# BladeCore-M54.net
KiCad netlist of a schematic drawn in EAGLE
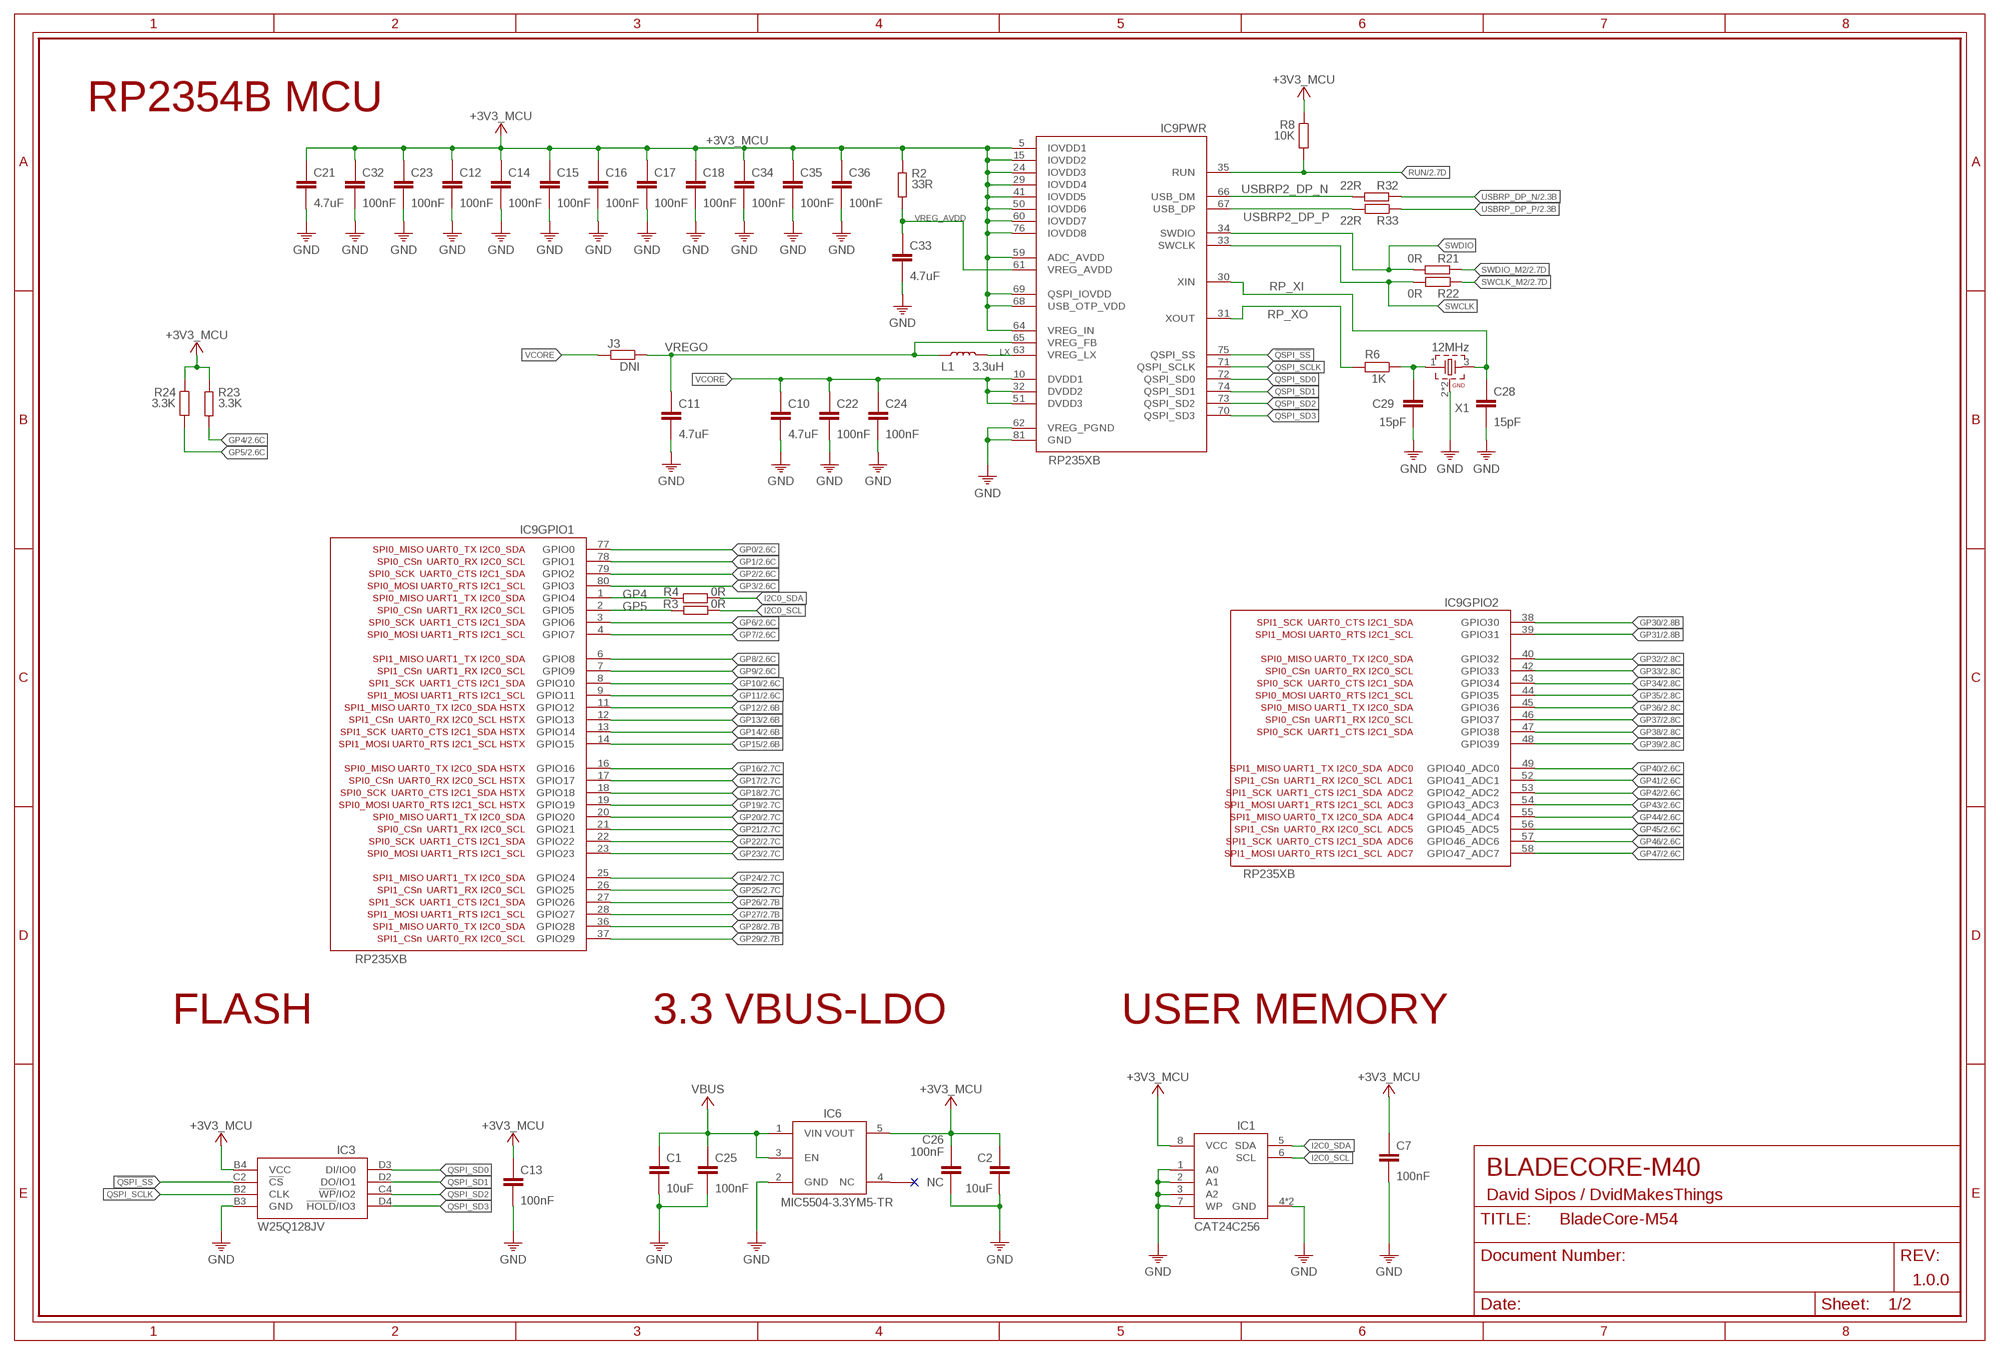
[diagram p0: schematic, sheet 1]
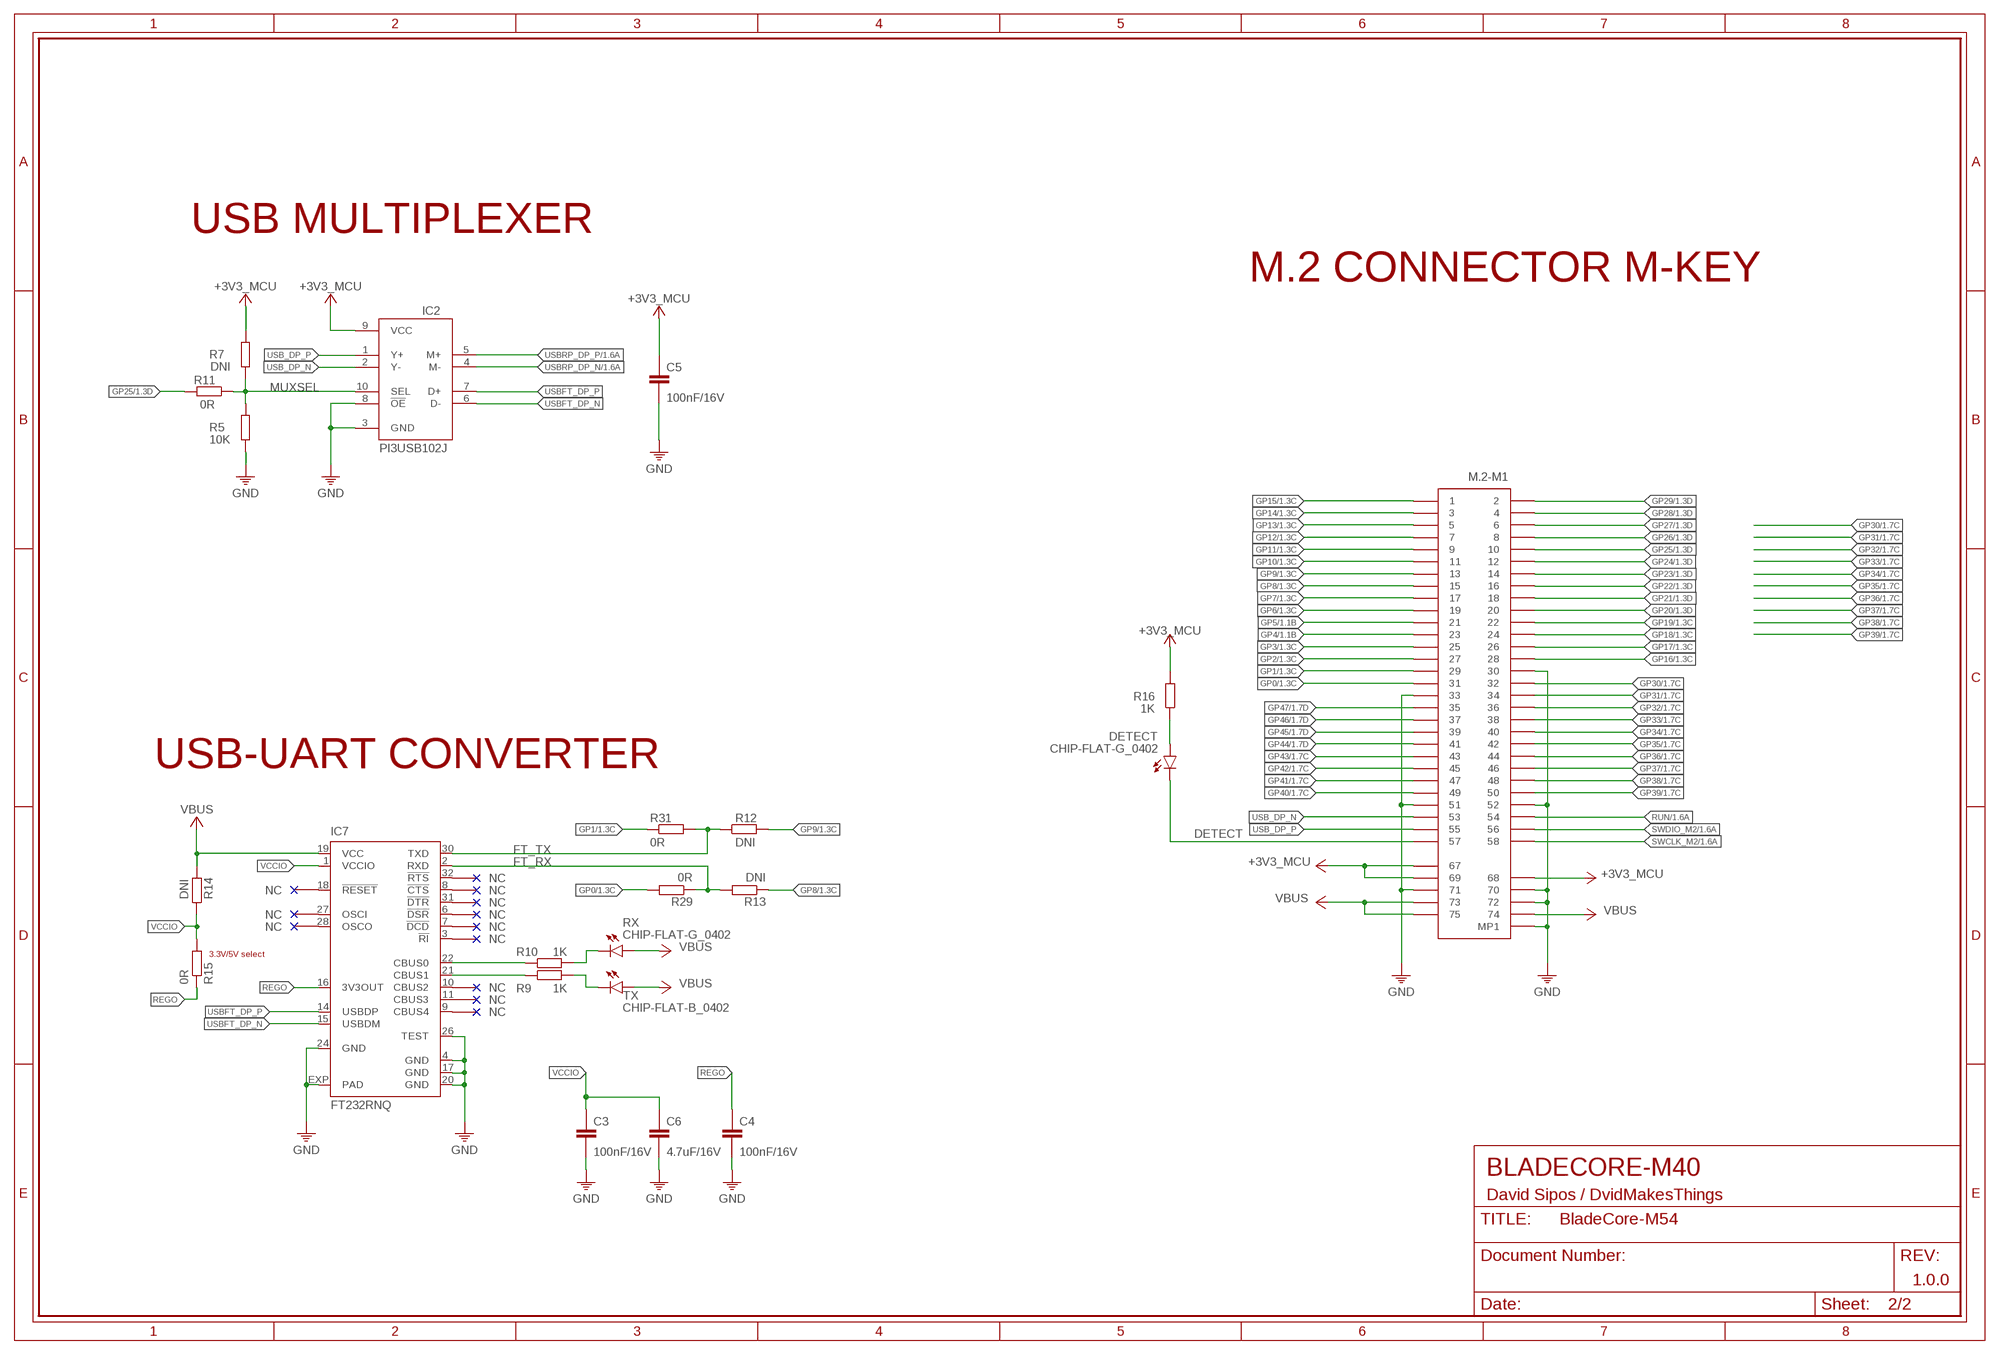
[diagram p1: schematic, sheet 2]

(export (version "E")
  (design (tool "Eeschema 10.0.6"))
  (components
    (comp (ref "C1")
      (value "10uF")
      (footprint "eagle-import:0805")
      (libsource (lib "eagle-import") (part "C0805"))
    )
    (comp (ref "C2")
      (value "10uF")
      (footprint "eagle-import:0805")
      (libsource (lib "eagle-import") (part "C0805"))
    )
    (comp (ref "C7")
      (value "100nF")
      (footprint "eagle-import:0201")
      (libsource (lib "eagle-import") (part "C-0201"))
    )
    (comp (ref "C10")
      (value "4.7uF")
      (footprint "eagle-import:0201")
      (libsource (lib "eagle-import") (part "C-0201"))
    )
    (comp (ref "C11")
      (value "4.7uF")
      (footprint "eagle-import:0201")
      (libsource (lib "eagle-import") (part "C-0201"))
    )
    (comp (ref "C12")
      (value "100nF")
      (footprint "eagle-import:0201")
      (libsource (lib "eagle-import") (part "C-0201"))
    )
    (comp (ref "C13")
      (value "100nF")
      (footprint "eagle-import:0201")
      (libsource (lib "eagle-import") (part "C-0201"))
    )
    (comp (ref "C14")
      (value "100nF")
      (footprint "eagle-import:0201")
      (libsource (lib "eagle-import") (part "C-0201"))
    )
    (comp (ref "C15")
      (value "100nF")
      (footprint "eagle-import:0201")
      (libsource (lib "eagle-import") (part "C-0201"))
    )
    (comp (ref "C16")
      (value "100nF")
      (footprint "eagle-import:0201")
      (libsource (lib "eagle-import") (part "C-0201"))
    )
    (comp (ref "C17")
      (value "100nF")
      (footprint "eagle-import:0201")
      (libsource (lib "eagle-import") (part "C-0201"))
    )
    (comp (ref "C18")
      (value "100nF")
      (footprint "eagle-import:0201")
      (libsource (lib "eagle-import") (part "C-0201"))
    )
    (comp (ref "C21")
      (value "4.7uF")
      (footprint "eagle-import:C0402")
      (libsource (lib "eagle-import") (part "C-0402"))
    )
    (comp (ref "C22")
      (value "100nF")
      (footprint "eagle-import:0201")
      (libsource (lib "eagle-import") (part "C-0201"))
    )
    (comp (ref "C23")
      (value "100nF")
      (footprint "eagle-import:0201")
      (libsource (lib "eagle-import") (part "C-0201"))
    )
    (comp (ref "C24")
      (value "100nF")
      (footprint "eagle-import:0201")
      (libsource (lib "eagle-import") (part "C-0201"))
    )
    (comp (ref "C25")
      (value "100nF")
      (footprint "eagle-import:0201")
      (libsource (lib "eagle-import") (part "C-0201"))
    )
    (comp (ref "C26")
      (value "100nF")
      (footprint "eagle-import:0201")
      (libsource (lib "eagle-import") (part "C-0201"))
    )
    (comp (ref "C28")
      (value "15pF")
      (footprint "eagle-import:0201")
      (libsource (lib "eagle-import") (part "C-0201"))
    )
    (comp (ref "C29")
      (value "15pF")
      (footprint "eagle-import:0201")
      (libsource (lib "eagle-import") (part "C-0201"))
    )
    (comp (ref "C32")
      (value "100nF")
      (footprint "eagle-import:0201")
      (libsource (lib "eagle-import") (part "C-0201"))
    )
    (comp (ref "C33")
      (value "4.7uF")
      (footprint "eagle-import:0201")
      (libsource (lib "eagle-import") (part "C-0201"))
    )
    (comp (ref "C34")
      (value "100nF")
      (footprint "eagle-import:0201")
      (libsource (lib "eagle-import") (part "C-0201"))
    )
    (comp (ref "C35")
      (value "100nF")
      (footprint "eagle-import:0201")
      (libsource (lib "eagle-import") (part "C-0201"))
    )
    (comp (ref "C36")
      (value "100nF")
      (footprint "eagle-import:0201")
      (libsource (lib "eagle-import") (part "C-0201"))
    )
    (comp (ref "IC1")
      (value "CAT24C512HU5IGT3")
      (footprint "eagle-import:SON50P300X200X50-9T130X140N")
      (libsource (lib "eagle-import") (part "CAT24C256-HU4"))
    )
    (comp (ref "IC3")
      (value "W25Q128JVCIQ TR")
      (footprint "eagle-import:BGA24C100P4X6_800X600X120N")
      (libsource (lib "eagle-import") (part "W25Q128JVC"))
    )
    (comp (ref "IC6")
      (value "MIC5504-3.3YM5-TR")
      (footprint "eagle-import:SOT23-5")
      (libsource (lib "eagle-import") (part "MIC5504-3.3YM5-TR"))
    )
    (comp (ref "IC9")
      (value "RP235XB")
      (footprint "eagle-import:QFN80-10X10")
      (libsource (lib "eagle-import") (part "RP235XB"))
    )
    (comp (ref "J3")
      (value "DNI")
      (footprint "eagle-import:R0201")
      (libsource (lib "eagle-import") (part "R0201"))
    )
    (comp (ref "L1")
      (value "3.3uH")
      (footprint "eagle-import:SRR5228A")
      (libsource (lib "eagle-import") (part "L"))
    )
    (comp (ref "R2")
      (value "33R")
      (footprint "eagle-import:R0201")
      (libsource (lib "eagle-import") (part "R0201"))
    )
    (comp (ref "R3")
      (value "0R")
      (footprint "eagle-import:R0201")
      (libsource (lib "eagle-import") (part "R0201"))
    )
    (comp (ref "R4")
      (value "0R")
      (footprint "eagle-import:R0201")
      (libsource (lib "eagle-import") (part "R0201"))
    )
    (comp (ref "R6")
      (value "1K")
      (footprint "eagle-import:R0201")
      (libsource (lib "eagle-import") (part "R0201"))
    )
    (comp (ref "R8")
      (value "10K")
      (footprint "eagle-import:R0201")
      (libsource (lib "eagle-import") (part "R0201"))
    )
    (comp (ref "R21")
      (value "0R")
      (footprint "eagle-import:R0201")
      (libsource (lib "eagle-import") (part "R0201"))
    )
    (comp (ref "R22")
      (value "0R")
      (footprint "eagle-import:R0201")
      (libsource (lib "eagle-import") (part "R0201"))
    )
    (comp (ref "R23")
      (value "3.3K")
      (footprint "eagle-import:R0201")
      (libsource (lib "eagle-import") (part "R0201"))
    )
    (comp (ref "R24")
      (value "3.3K")
      (footprint "eagle-import:R0201")
      (libsource (lib "eagle-import") (part "R0201"))
    )
    (comp (ref "R32")
      (value "22R")
      (footprint "eagle-import:R0201")
      (libsource (lib "eagle-import") (part "R0201"))
    )
    (comp (ref "R33")
      (value "22R")
      (footprint "eagle-import:R0201")
      (libsource (lib "eagle-import") (part "R0201"))
    )
    (comp (ref "X1")
      (value "12MHz")
      (footprint "eagle-import:WE-XTAL_CFPX-180")
      (fields (field (name "TOLERANCE") "±20ppm"))
      (libsource (lib "eagle-import") (part "WE-XTAL_CFPX-180_830069944"))
    )
    (comp (ref "C3")
      (value "100nF/16V")
      (footprint "eagle-import:0201")
      (libsource (lib "eagle-import") (part "C-0201"))
    )
    (comp (ref "C4")
      (value "100nF/16V")
      (footprint "eagle-import:0201")
      (libsource (lib "eagle-import") (part "C-0201"))
    )
    (comp (ref "C5")
      (value "100nF/16V")
      (footprint "eagle-import:0201")
      (libsource (lib "eagle-import") (part "C-0201"))
    )
    (comp (ref "C6")
      (value "4.7uF/16V")
      (footprint "eagle-import:0201")
      (libsource (lib "eagle-import") (part "C-0201"))
    )
    (comp (ref "DETECT")
      (value "CHIP-FLAT-G_0402")
      (footprint "eagle-import:LEDC1005X25N_FLAT-G")
      (libsource (lib "eagle-import") (part "CHIP-FLAT-G_0402"))
    )
    (comp (ref "IC2")
      (value "PI3USB102J")
      (footprint "eagle-import:QFN40P120X140X35-10N")
      (libsource (lib "eagle-import") (part "PI3USB102JXUCEX"))
    )
    (comp (ref "IC7")
      (value "FT232RNQ")
      (footprint "eagle-import:QFN32")
      (libsource (lib "eagle-import") (part "FT232RQ"))
    )
    (comp (ref "M.2-M1")
      (value "M.2-M-KEY")
      (footprint "eagle-import:M.2-M-KEY")
      (libsource (lib "eagle-import") (part "M.2-M-KEY"))
    )
    (comp (ref "R5")
      (value "10K")
      (footprint "eagle-import:R0201")
      (libsource (lib "eagle-import") (part "R0201"))
    )
    (comp (ref "R7")
      (value "DNI")
      (footprint "eagle-import:R0201")
      (libsource (lib "eagle-import") (part "R0201"))
    )
    (comp (ref "R9")
      (value "1K")
      (footprint "eagle-import:R0201")
      (libsource (lib "eagle-import") (part "R0201"))
    )
    (comp (ref "R10")
      (value "1K")
      (footprint "eagle-import:R0201")
      (libsource (lib "eagle-import") (part "R0201"))
    )
    (comp (ref "R11")
      (value "0R")
      (footprint "eagle-import:R0201")
      (libsource (lib "eagle-import") (part "R0201"))
    )
    (comp (ref "R12")
      (value "DNI")
      (footprint "eagle-import:R0201")
      (libsource (lib "eagle-import") (part "R0201"))
    )
    (comp (ref "R13")
      (value "DNI")
      (footprint "eagle-import:R0201")
      (libsource (lib "eagle-import") (part "R0201"))
    )
    (comp (ref "R14")
      (value "DNI")
      (footprint "eagle-import:R0201")
      (libsource (lib "eagle-import") (part "R0201"))
    )
    (comp (ref "R15")
      (value "0R")
      (footprint "eagle-import:R0201")
      (libsource (lib "eagle-import") (part "R0201"))
    )
    (comp (ref "R16")
      (value "1K")
      (footprint "eagle-import:R0201")
      (libsource (lib "eagle-import") (part "R0201"))
    )
    (comp (ref "R29")
      (value "0R")
      (footprint "eagle-import:R0201")
      (libsource (lib "eagle-import") (part "R0201"))
    )
    (comp (ref "R31")
      (value "0R")
      (footprint "eagle-import:R0201")
      (libsource (lib "eagle-import") (part "R0201"))
    )
    (comp (ref "RX")
      (value "CHIP-FLAT-G_0402")
      (footprint "eagle-import:LEDC1005X25N_FLAT-G")
      (libsource (lib "eagle-import") (part "CHIP-FLAT-G_0402"))
    )
    (comp (ref "TX")
      (value "CHIP-FLAT-B_0402")
      (footprint "eagle-import:LEDC1005X25N_FLAT-B")
      (libsource (lib "eagle-import") (part "CHIP-FLAT-B_0402"))
    )
  )
  (nets
    (net (code "1") (name "+3V3_MCU") (class "Default")
      (node (ref "C12") (pin "1") (pinfunction "1_1") (pintype "passive"))
      (node (ref "C13") (pin "1") (pinfunction "1_1") (pintype "passive"))
      (node (ref "C14") (pin "1") (pinfunction "1_1") (pintype "passive"))
      (node (ref "C15") (pin "1") (pinfunction "1_1") (pintype "passive"))
      (node (ref "C16") (pin "1") (pinfunction "1_1") (pintype "passive"))
      (node (ref "C17") (pin "1") (pinfunction "1_1") (pintype "passive"))
      (node (ref "C18") (pin "1") (pinfunction "1_1") (pintype "passive"))
      (node (ref "C2") (pin "1") (pinfunction "1_1") (pintype "passive"))
      (node (ref "C21") (pin "1") (pinfunction "1_1") (pintype "passive"))
      (node (ref "C23") (pin "1") (pinfunction "1_1") (pintype "passive"))
      (node (ref "C26") (pin "1") (pinfunction "1_1") (pintype "passive"))
      (node (ref "C32") (pin "1") (pinfunction "1_1") (pintype "passive"))
      (node (ref "C34") (pin "1") (pinfunction "1_1") (pintype "passive"))
      (node (ref "C35") (pin "1") (pinfunction "1_1") (pintype "passive"))
      (node (ref "C36") (pin "1") (pinfunction "1_1") (pintype "passive"))
      (node (ref "C5") (pin "1") (pinfunction "1_1") (pintype "passive"))
      (node (ref "C7") (pin "1") (pinfunction "1_1") (pintype "passive"))
      (node (ref "IC1") (pin "8") (pinfunction "VCC_8") (pintype "power_in"))
      (node (ref "IC2") (pin "9") (pinfunction "VCC_9") (pintype "power_in"))
      (node (ref "IC3") (pin "B4") (pinfunction "VCC_B4") (pintype "power_in"))
      (node (ref "IC6") (pin "5") (pinfunction "VOUT_5") (pintype "bidirectional"))
      (node (ref "IC9") (pin "15") (pinfunction "IOVDD2_15") (pintype "power_in"))
      (node (ref "IC9") (pin "24") (pinfunction "IOVDD3_24") (pintype "power_in"))
      (node (ref "IC9") (pin "29") (pinfunction "IOVDD4_29") (pintype "power_in"))
      (node (ref "IC9") (pin "41") (pinfunction "IOVDD5_41") (pintype "power_in"))
      (node (ref "IC9") (pin "5") (pinfunction "IOVDD1_5") (pintype "power_in"))
      (node (ref "IC9") (pin "50") (pinfunction "IOVDD6_50") (pintype "power_in"))
      (node (ref "IC9") (pin "59") (pinfunction "ADC_AVDD_59") (pintype "power_in"))
      (node (ref "IC9") (pin "60") (pinfunction "IOVDD7_60") (pintype "power_in"))
      (node (ref "IC9") (pin "64") (pinfunction "VREG_IN_64") (pintype "power_in"))
      (node (ref "IC9") (pin "68") (pinfunction "USB_OTP_VDD_68") (pintype "power_in"))
      (node (ref "IC9") (pin "69") (pinfunction "QSPI_IOVDD_69") (pintype "power_in"))
      (node (ref "IC9") (pin "76") (pinfunction "IOVDD8_76") (pintype "power_in"))
      (node (ref "M.2-M1") (pin "P$67") (pinfunction "67_P$67") (pintype "bidirectional"))
      (node (ref "M.2-M1") (pin "P$68") (pinfunction "68_P$68") (pintype "bidirectional"))
      (node (ref "M.2-M1") (pin "P$69") (pinfunction "69_P$69") (pintype "bidirectional"))
      (node (ref "R16") (pin "2") (pinfunction "2_2") (pintype "passive"))
      (node (ref "R2") (pin "1") (pinfunction "1_1") (pintype "passive"))
      (node (ref "R23") (pin "1") (pinfunction "1_1") (pintype "passive"))
      (node (ref "R24") (pin "1") (pinfunction "1_1") (pintype "passive"))
      (node (ref "R7") (pin "2") (pinfunction "2_2") (pintype "passive"))
      (node (ref "R8") (pin "1") (pinfunction "1_1") (pintype "passive"))
    )
    (net (code "2") (name "DETECT") (class "Default")
      (node (ref "DETECT") (pin "C") (pinfunction "C_C") (pintype "passive"))
      (node (ref "M.2-M1") (pin "P$57") (pinfunction "57_P$57") (pintype "bidirectional"))
    )
    (net (code "3") (name "FT_RX") (class "Default")
      (node (ref "IC7") (pin "2") (pinfunction "RXD_2") (pintype "input"))
      (node (ref "R13") (pin "2") (pinfunction "2_2") (pintype "passive"))
      (node (ref "R29") (pin "1") (pinfunction "1_1") (pintype "passive"))
    )
    (net (code "4") (name "FT_TX") (class "Default")
      (node (ref "IC7") (pin "30") (pinfunction "TXD_30") (pintype "output"))
      (node (ref "R12") (pin "1") (pinfunction "1_1") (pintype "passive"))
      (node (ref "R31") (pin "2") (pinfunction "2_2") (pintype "passive"))
    )
    (net (code "5") (name "GND") (class "Default")
      (node (ref "C1") (pin "2") (pinfunction "2_2") (pintype "passive"))
      (node (ref "C10") (pin "2") (pinfunction "2_2") (pintype "passive"))
      (node (ref "C11") (pin "2") (pinfunction "2_2") (pintype "passive"))
      (node (ref "C12") (pin "2") (pinfunction "2_2") (pintype "passive"))
      (node (ref "C13") (pin "2") (pinfunction "2_2") (pintype "passive"))
      (node (ref "C14") (pin "2") (pinfunction "2_2") (pintype "passive"))
      (node (ref "C15") (pin "2") (pinfunction "2_2") (pintype "passive"))
      (node (ref "C16") (pin "2") (pinfunction "2_2") (pintype "passive"))
      (node (ref "C17") (pin "2") (pinfunction "2_2") (pintype "passive"))
      (node (ref "C18") (pin "2") (pinfunction "2_2") (pintype "passive"))
      (node (ref "C2") (pin "2") (pinfunction "2_2") (pintype "passive"))
      (node (ref "C21") (pin "2") (pinfunction "2_2") (pintype "passive"))
      (node (ref "C22") (pin "2") (pinfunction "2_2") (pintype "passive"))
      (node (ref "C23") (pin "2") (pinfunction "2_2") (pintype "passive"))
      (node (ref "C24") (pin "2") (pinfunction "2_2") (pintype "passive"))
      (node (ref "C25") (pin "2") (pinfunction "2_2") (pintype "passive"))
      (node (ref "C26") (pin "2") (pinfunction "2_2") (pintype "passive"))
      (node (ref "C28") (pin "2") (pinfunction "2_2") (pintype "passive"))
      (node (ref "C29") (pin "2") (pinfunction "2_2") (pintype "passive"))
      (node (ref "C3") (pin "2") (pinfunction "2_2") (pintype "passive"))
      (node (ref "C32") (pin "2") (pinfunction "2_2") (pintype "passive"))
      (node (ref "C33") (pin "2") (pinfunction "2_2") (pintype "passive"))
      (node (ref "C34") (pin "2") (pinfunction "2_2") (pintype "passive"))
      (node (ref "C35") (pin "2") (pinfunction "2_2") (pintype "passive"))
      (node (ref "C36") (pin "2") (pinfunction "2_2") (pintype "passive"))
      (node (ref "C4") (pin "2") (pinfunction "2_2") (pintype "passive"))
      (node (ref "C5") (pin "2") (pinfunction "2_2") (pintype "passive"))
      (node (ref "C6") (pin "2") (pinfunction "2_2") (pintype "passive"))
      (node (ref "C7") (pin "2") (pinfunction "2_2") (pintype "passive"))
      (node (ref "IC1") (pin "1") (pinfunction "A0_1") (pintype "bidirectional"))
      (node (ref "IC1") (pin "2") (pinfunction "A1_2") (pintype "bidirectional"))
      (node (ref "IC1") (pin "3") (pinfunction "A2_3") (pintype "bidirectional"))
      (node (ref "IC1") (pin "4") (pinfunction "GND_4") (pintype "power_in"))
      (node (ref "IC1") (pin "7") (pinfunction "WP_7") (pintype "bidirectional"))
      (node (ref "IC1") (pin "9") (pinfunction "GND_9") (pintype "power_in"))
      (node (ref "IC2") (pin "3") (pinfunction "GND_3") (pintype "power_in"))
      (node (ref "IC2") (pin "8") (pinfunction "~{OE}_8") (pintype "input"))
      (node (ref "IC3") (pin "B3") (pinfunction "GND_B3") (pintype "power_in"))
      (node (ref "IC6") (pin "2") (pinfunction "GND_2") (pintype "bidirectional"))
      (node (ref "IC7") (pin "17") (pinfunction "GND_17") (pintype "power_in"))
      (node (ref "IC7") (pin "20") (pinfunction "GND_20") (pintype "power_in"))
      (node (ref "IC7") (pin "24") (pinfunction "GND_24") (pintype "power_in"))
      (node (ref "IC7") (pin "26") (pinfunction "TEST_26") (pintype "input"))
      (node (ref "IC7") (pin "4") (pinfunction "GND_4") (pintype "power_in"))
      (node (ref "IC7") (pin "EXP") (pinfunction "PAD_EXP") (pintype "power_in"))
      (node (ref "IC9") (pin "62") (pinfunction "VREG_PGND_62") (pintype "power_in"))
      (node (ref "IC9") (pin "81") (pinfunction "GND_81") (pintype "power_in"))
      (node (ref "M.2-M1") (pin "MT1") (pinfunction "MP1_MT1") (pintype "bidirectional"))
      (node (ref "M.2-M1") (pin "P$30") (pinfunction "30_P$30") (pintype "bidirectional"))
      (node (ref "M.2-M1") (pin "P$33") (pinfunction "33_P$33") (pintype "bidirectional"))
      (node (ref "M.2-M1") (pin "P$51") (pinfunction "51_P$51") (pintype "bidirectional"))
      (node (ref "M.2-M1") (pin "P$52") (pinfunction "52_P$52") (pintype "bidirectional"))
      (node (ref "M.2-M1") (pin "P$70") (pinfunction "70_P$70") (pintype "bidirectional"))
      (node (ref "M.2-M1") (pin "P$71") (pinfunction "71_P$71") (pintype "bidirectional"))
      (node (ref "M.2-M1") (pin "P$72") (pinfunction "72_P$72") (pintype "bidirectional"))
      (node (ref "R5") (pin "1") (pinfunction "1_1") (pintype "passive"))
      (node (ref "X1") (pin "2") (pinfunction "GND_2") (pintype "passive"))
      (node (ref "X1") (pin "4") (pinfunction "GND_4") (pintype "passive"))
    )
    (net (code "6") (name "GP0") (class "Default")
      (node (ref "IC9") (pin "77") (pinfunction "GPIO0_77") (pintype "bidirectional"))
      (node (ref "M.2-M1") (pin "P$31") (pinfunction "31_P$31") (pintype "bidirectional"))
      (node (ref "R29") (pin "2") (pinfunction "2_2") (pintype "passive"))
    )
    (net (code "7") (name "GP1") (class "Default")
      (node (ref "IC9") (pin "78") (pinfunction "GPIO1_78") (pintype "bidirectional"))
      (node (ref "M.2-M1") (pin "P$29") (pinfunction "29_P$29") (pintype "bidirectional"))
      (node (ref "R31") (pin "1") (pinfunction "1_1") (pintype "passive"))
    )
    (net (code "8") (name "GP2") (class "Default")
      (node (ref "IC9") (pin "79") (pinfunction "GPIO2_79") (pintype "bidirectional"))
      (node (ref "M.2-M1") (pin "P$27") (pinfunction "27_P$27") (pintype "bidirectional"))
    )
    (net (code "9") (name "GP3") (class "Default")
      (node (ref "IC9") (pin "80") (pinfunction "GPIO3_80") (pintype "bidirectional"))
      (node (ref "M.2-M1") (pin "P$25") (pinfunction "25_P$25") (pintype "bidirectional"))
    )
    (net (code "10") (name "GP4") (class "Default")
      (node (ref "IC9") (pin "1") (pinfunction "GPIO4_1") (pintype "bidirectional"))
      (node (ref "M.2-M1") (pin "P$23") (pinfunction "23_P$23") (pintype "bidirectional"))
      (node (ref "R23") (pin "2") (pinfunction "2_2") (pintype "passive"))
      (node (ref "R4") (pin "1") (pinfunction "1_1") (pintype "passive"))
    )
    (net (code "11") (name "GP5") (class "Default")
      (node (ref "IC9") (pin "2") (pinfunction "GPIO5_2") (pintype "bidirectional"))
      (node (ref "M.2-M1") (pin "P$21") (pinfunction "21_P$21") (pintype "bidirectional"))
      (node (ref "R24") (pin "2") (pinfunction "2_2") (pintype "passive"))
      (node (ref "R3") (pin "1") (pinfunction "1_1") (pintype "passive"))
    )
    (net (code "12") (name "GP6") (class "Default")
      (node (ref "IC9") (pin "3") (pinfunction "GPIO6_3") (pintype "bidirectional"))
      (node (ref "M.2-M1") (pin "P$19") (pinfunction "19_P$19") (pintype "bidirectional"))
    )
    (net (code "13") (name "GP7") (class "Default")
      (node (ref "IC9") (pin "4") (pinfunction "GPIO7_4") (pintype "bidirectional"))
      (node (ref "M.2-M1") (pin "P$17") (pinfunction "17_P$17") (pintype "bidirectional"))
    )
    (net (code "14") (name "GP8") (class "Default")
      (node (ref "IC9") (pin "6") (pinfunction "GPIO8_6") (pintype "bidirectional"))
      (node (ref "M.2-M1") (pin "P$15") (pinfunction "15_P$15") (pintype "bidirectional"))
      (node (ref "R13") (pin "1") (pinfunction "1_1") (pintype "passive"))
    )
    (net (code "15") (name "GP9") (class "Default")
      (node (ref "IC9") (pin "7") (pinfunction "GPIO9_7") (pintype "bidirectional"))
      (node (ref "M.2-M1") (pin "P$13") (pinfunction "13_P$13") (pintype "bidirectional"))
      (node (ref "R12") (pin "2") (pinfunction "2_2") (pintype "passive"))
    )
    (net (code "16") (name "GP10") (class "Default")
      (node (ref "IC9") (pin "8") (pinfunction "GPIO10_8") (pintype "bidirectional"))
      (node (ref "M.2-M1") (pin "P$11") (pinfunction "11_P$11") (pintype "bidirectional"))
    )
    (net (code "17") (name "GP11") (class "Default")
      (node (ref "IC9") (pin "9") (pinfunction "GPIO11_9") (pintype "bidirectional"))
      (node (ref "M.2-M1") (pin "P$9") (pinfunction "9_P$9") (pintype "bidirectional"))
    )
    (net (code "18") (name "GP12") (class "Default")
      (node (ref "IC9") (pin "11") (pinfunction "GPIO12_11") (pintype "bidirectional"))
      (node (ref "M.2-M1") (pin "P$7") (pinfunction "7_P$7") (pintype "bidirectional"))
    )
    (net (code "19") (name "GP13") (class "Default")
      (node (ref "IC9") (pin "12") (pinfunction "GPIO13_12") (pintype "bidirectional"))
      (node (ref "M.2-M1") (pin "P$5") (pinfunction "5_P$5") (pintype "bidirectional"))
    )
    (net (code "20") (name "GP14") (class "Default")
      (node (ref "IC9") (pin "13") (pinfunction "GPIO14_13") (pintype "bidirectional"))
      (node (ref "M.2-M1") (pin "P$3") (pinfunction "3_P$3") (pintype "bidirectional"))
    )
    (net (code "21") (name "GP15") (class "Default")
      (node (ref "IC9") (pin "14") (pinfunction "GPIO15_14") (pintype "bidirectional"))
      (node (ref "M.2-M1") (pin "P$1") (pinfunction "1_P$1") (pintype "bidirectional"))
    )
    (net (code "22") (name "GP16") (class "Default")
      (node (ref "IC9") (pin "16") (pinfunction "GPIO16_16") (pintype "bidirectional"))
      (node (ref "M.2-M1") (pin "P$28") (pinfunction "28_P$28") (pintype "bidirectional"))
    )
    (net (code "23") (name "GP17") (class "Default")
      (node (ref "IC9") (pin "17") (pinfunction "GPIO17_17") (pintype "bidirectional"))
      (node (ref "M.2-M1") (pin "P$26") (pinfunction "26_P$26") (pintype "bidirectional"))
    )
    (net (code "24") (name "GP18") (class "Default")
      (node (ref "IC9") (pin "18") (pinfunction "GPIO18_18") (pintype "bidirectional"))
      (node (ref "M.2-M1") (pin "P$24") (pinfunction "24_P$24") (pintype "bidirectional"))
    )
    (net (code "25") (name "GP19") (class "Default")
      (node (ref "IC9") (pin "19") (pinfunction "GPIO19_19") (pintype "bidirectional"))
      (node (ref "M.2-M1") (pin "P$22") (pinfunction "22_P$22") (pintype "bidirectional"))
    )
    (net (code "26") (name "GP20") (class "Default")
      (node (ref "IC9") (pin "20") (pinfunction "GPIO20_20") (pintype "bidirectional"))
      (node (ref "M.2-M1") (pin "P$20") (pinfunction "20_P$20") (pintype "bidirectional"))
    )
    (net (code "27") (name "GP21") (class "Default")
      (node (ref "IC9") (pin "21") (pinfunction "GPIO21_21") (pintype "bidirectional"))
      (node (ref "M.2-M1") (pin "P$18") (pinfunction "18_P$18") (pintype "bidirectional"))
    )
    (net (code "28") (name "GP22") (class "Default")
      (node (ref "IC9") (pin "22") (pinfunction "GPIO22_22") (pintype "bidirectional"))
      (node (ref "M.2-M1") (pin "P$16") (pinfunction "16_P$16") (pintype "bidirectional"))
    )
    (net (code "29") (name "GP23") (class "Default")
      (node (ref "IC9") (pin "23") (pinfunction "GPIO23_23") (pintype "bidirectional"))
      (node (ref "M.2-M1") (pin "P$14") (pinfunction "14_P$14") (pintype "bidirectional"))
    )
    (net (code "30") (name "GP24") (class "Default")
      (node (ref "IC9") (pin "25") (pinfunction "GPIO24_25") (pintype "bidirectional"))
      (node (ref "M.2-M1") (pin "P$12") (pinfunction "12_P$12") (pintype "bidirectional"))
    )
    (net (code "31") (name "GP25") (class "Default")
      (node (ref "IC9") (pin "26") (pinfunction "GPIO25_26") (pintype "bidirectional"))
      (node (ref "M.2-M1") (pin "P$10") (pinfunction "10_P$10") (pintype "bidirectional"))
      (node (ref "R11") (pin "2") (pinfunction "2_2") (pintype "passive"))
    )
    (net (code "32") (name "GP26") (class "Default")
      (node (ref "IC9") (pin "27") (pinfunction "GPIO26_27") (pintype "bidirectional"))
      (node (ref "M.2-M1") (pin "P$8") (pinfunction "8_P$8") (pintype "bidirectional"))
    )
    (net (code "33") (name "GP27") (class "Default")
      (node (ref "IC9") (pin "28") (pinfunction "GPIO27_28") (pintype "bidirectional"))
      (node (ref "M.2-M1") (pin "P$6") (pinfunction "6_P$6") (pintype "bidirectional"))
    )
    (net (code "34") (name "GP28") (class "Default")
      (node (ref "IC9") (pin "36") (pinfunction "GPIO28_36") (pintype "bidirectional"))
      (node (ref "M.2-M1") (pin "P$4") (pinfunction "4_P$4") (pintype "bidirectional"))
    )
    (net (code "35") (name "GP29") (class "Default")
      (node (ref "IC9") (pin "37") (pinfunction "GPIO29_37") (pintype "bidirectional"))
      (node (ref "M.2-M1") (pin "P$2") (pinfunction "2_P$2") (pintype "bidirectional"))
    )
    (net (code "36") (name "GP30") (class "Default")
      (node (ref "IC9") (pin "38") (pinfunction "GPIO30_38") (pintype "bidirectional"))
      (node (ref "M.2-M1") (pin "P$32") (pinfunction "32_P$32") (pintype "bidirectional"))
    )
    (net (code "37") (name "GP31") (class "Default")
      (node (ref "IC9") (pin "39") (pinfunction "GPIO31_39") (pintype "bidirectional"))
      (node (ref "M.2-M1") (pin "P$34") (pinfunction "34_P$34") (pintype "bidirectional"))
    )
    (net (code "38") (name "GP32") (class "Default")
      (node (ref "IC9") (pin "40") (pinfunction "GPIO32_40") (pintype "bidirectional"))
      (node (ref "M.2-M1") (pin "P$36") (pinfunction "36_P$36") (pintype "bidirectional"))
    )
    (net (code "39") (name "GP33") (class "Default")
      (node (ref "IC9") (pin "42") (pinfunction "GPIO33_42") (pintype "bidirectional"))
      (node (ref "M.2-M1") (pin "P$38") (pinfunction "38_P$38") (pintype "bidirectional"))
    )
    (net (code "40") (name "GP34") (class "Default")
      (node (ref "IC9") (pin "43") (pinfunction "GPIO34_43") (pintype "bidirectional"))
      (node (ref "M.2-M1") (pin "P$40") (pinfunction "40_P$40") (pintype "bidirectional"))
    )
    (net (code "41") (name "GP35") (class "Default")
      (node (ref "IC9") (pin "44") (pinfunction "GPIO35_44") (pintype "bidirectional"))
      (node (ref "M.2-M1") (pin "P$42") (pinfunction "42_P$42") (pintype "bidirectional"))
    )
    (net (code "42") (name "GP36") (class "Default")
      (node (ref "IC9") (pin "45") (pinfunction "GPIO36_45") (pintype "bidirectional"))
      (node (ref "M.2-M1") (pin "P$44") (pinfunction "44_P$44") (pintype "bidirectional"))
    )
    (net (code "43") (name "GP37") (class "Default")
      (node (ref "IC9") (pin "46") (pinfunction "GPIO37_46") (pintype "bidirectional"))
      (node (ref "M.2-M1") (pin "P$46") (pinfunction "46_P$46") (pintype "bidirectional"))
    )
    (net (code "44") (name "GP38") (class "Default")
      (node (ref "IC9") (pin "47") (pinfunction "GPIO38_47") (pintype "bidirectional"))
      (node (ref "M.2-M1") (pin "P$48") (pinfunction "48_P$48") (pintype "bidirectional"))
    )
    (net (code "45") (name "GP39") (class "Default")
      (node (ref "IC9") (pin "48") (pinfunction "GPIO39_48") (pintype "bidirectional"))
      (node (ref "M.2-M1") (pin "P$50") (pinfunction "50_P$50") (pintype "bidirectional"))
    )
    (net (code "46") (name "GP40") (class "Default")
      (node (ref "IC9") (pin "49") (pinfunction "GPIO40_ADC0_49") (pintype "bidirectional"))
      (node (ref "M.2-M1") (pin "P$49") (pinfunction "49_P$49") (pintype "bidirectional"))
    )
    (net (code "47") (name "GP41") (class "Default")
      (node (ref "IC9") (pin "52") (pinfunction "GPIO41_ADC1_52") (pintype "bidirectional"))
      (node (ref "M.2-M1") (pin "P$47") (pinfunction "47_P$47") (pintype "bidirectional"))
    )
    (net (code "48") (name "GP42") (class "Default")
      (node (ref "IC9") (pin "53") (pinfunction "GPIO42_ADC2_53") (pintype "bidirectional"))
      (node (ref "M.2-M1") (pin "P$45") (pinfunction "45_P$45") (pintype "bidirectional"))
    )
    (net (code "49") (name "GP43") (class "Default")
      (node (ref "IC9") (pin "54") (pinfunction "GPIO43_ADC3_54") (pintype "bidirectional"))
      (node (ref "M.2-M1") (pin "P$43") (pinfunction "43_P$43") (pintype "bidirectional"))
    )
    (net (code "50") (name "GP44") (class "Default")
      (node (ref "IC9") (pin "55") (pinfunction "GPIO44_ADC4_55") (pintype "bidirectional"))
      (node (ref "M.2-M1") (pin "P$41") (pinfunction "41_P$41") (pintype "bidirectional"))
    )
    (net (code "51") (name "GP45") (class "Default")
      (node (ref "IC9") (pin "56") (pinfunction "GPIO45_ADC5_56") (pintype "bidirectional"))
      (node (ref "M.2-M1") (pin "P$39") (pinfunction "39_P$39") (pintype "bidirectional"))
    )
    (net (code "52") (name "GP46") (class "Default")
      (node (ref "IC9") (pin "57") (pinfunction "GPIO46_ADC6_57") (pintype "bidirectional"))
      (node (ref "M.2-M1") (pin "P$37") (pinfunction "37_P$37") (pintype "bidirectional"))
    )
    (net (code "53") (name "GP47") (class "Default")
      (node (ref "IC9") (pin "58") (pinfunction "GPIO47_ADC7_58") (pintype "bidirectional"))
      (node (ref "M.2-M1") (pin "P$35") (pinfunction "35_P$35") (pintype "bidirectional"))
    )
    (net (code "54") (name "I2C0_SCL") (class "Default")
      (node (ref "IC1") (pin "6") (pinfunction "SCL_6") (pintype "bidirectional"))
      (node (ref "R3") (pin "2") (pinfunction "2_2") (pintype "passive"))
    )
    (net (code "55") (name "I2C0_SDA") (class "Default")
      (node (ref "IC1") (pin "5") (pinfunction "SDA_5") (pintype "bidirectional"))
      (node (ref "R4") (pin "2") (pinfunction "2_2") (pintype "passive"))
    )
    (net (code "56") (name "LX") (class "Default")
      (node (ref "IC9") (pin "63") (pinfunction "VREG_LX_63") (pintype "power_in"))
      (node (ref "L1") (pin "2") (pinfunction "2_2") (pintype "passive"))
    )
    (net (code "57") (name "MUXSEL") (class "Default")
      (node (ref "IC2") (pin "10") (pinfunction "SEL_10") (pintype "input"))
      (node (ref "R11") (pin "1") (pinfunction "1_1") (pintype "passive"))
      (node (ref "R5") (pin "2") (pinfunction "2_2") (pintype "passive"))
      (node (ref "R7") (pin "1") (pinfunction "1_1") (pintype "passive"))
    )
    (net (code "58") (name "Net-(C29-Pad1)") (class "Default")
      (node (ref "C29") (pin "1") (pinfunction "1_1") (pintype "passive"))
      (node (ref "R6") (pin "1") (pinfunction "1_1") (pintype "passive"))
      (node (ref "X1") (pin "1") (pinfunction "1_1") (pintype "passive"))
    )
    (net (code "59") (name "Net-(DETECT-PadA)") (class "Default")
      (node (ref "DETECT") (pin "A") (pinfunction "A_A") (pintype "passive"))
      (node (ref "R16") (pin "1") (pinfunction "1_1") (pintype "passive"))
    )
    (net (code "60") (name "Net-(IC7-CBUS0)") (class "Default")
      (node (ref "IC7") (pin "22") (pinfunction "CBUS0_22") (pintype "bidirectional"))
      (node (ref "R10") (pin "1") (pinfunction "1_1") (pintype "passive"))
    )
    (net (code "61") (name "Net-(IC7-CBUS1)") (class "Default")
      (node (ref "IC7") (pin "21") (pinfunction "CBUS1_21") (pintype "bidirectional"))
      (node (ref "R9") (pin "1") (pinfunction "1_1") (pintype "passive"))
    )
    (net (code "62") (name "Net-(R9-Pad2)") (class "Default")
      (node (ref "R9") (pin "2") (pinfunction "2_2") (pintype "passive"))
      (node (ref "TX") (pin "C") (pinfunction "C_C") (pintype "passive"))
    )
    (net (code "63") (name "Net-(R10-Pad2)") (class "Default")
      (node (ref "R10") (pin "2") (pinfunction "2_2") (pintype "passive"))
      (node (ref "RX") (pin "C") (pinfunction "C_C") (pintype "passive"))
    )
    (net (code "64") (name "QSPI_SCLK") (class "Default")
      (node (ref "IC3") (pin "B2") (pinfunction "CLK_B2") (pintype "bidirectional"))
      (node (ref "IC9") (pin "71") (pinfunction "QSPI_SCLK_71") (pintype "output"))
    )
    (net (code "65") (name "QSPI_SD0") (class "Default")
      (node (ref "IC3") (pin "D3") (pinfunction "DI/IO0_D3") (pintype "bidirectional"))
      (node (ref "IC9") (pin "72") (pinfunction "QSPI_SD0_72") (pintype "bidirectional"))
    )
    (net (code "66") (name "QSPI_SD1") (class "Default")
      (node (ref "IC3") (pin "D2") (pinfunction "DO/IO1_D2") (pintype "bidirectional"))
      (node (ref "IC9") (pin "74") (pinfunction "QSPI_SD1_74") (pintype "bidirectional"))
    )
    (net (code "67") (name "QSPI_SD2") (class "Default")
      (node (ref "IC3") (pin "C4") (pinfunction "~{WP}/IO2_C4") (pintype "bidirectional"))
      (node (ref "IC9") (pin "73") (pinfunction "QSPI_SD2_73") (pintype "bidirectional"))
    )
    (net (code "68") (name "QSPI_SD3") (class "Default")
      (node (ref "IC3") (pin "D4") (pinfunction "~{HOLD}/IO3_D4") (pintype "bidirectional"))
      (node (ref "IC9") (pin "70") (pinfunction "QSPI_SD3_70") (pintype "bidirectional"))
    )
    (net (code "69") (name "REGO") (class "Default")
      (node (ref "C4") (pin "1") (pinfunction "1_1") (pintype "passive"))
      (node (ref "IC7") (pin "16") (pinfunction "3V3OUT_16") (pintype "output"))
      (node (ref "R15") (pin "1") (pinfunction "1_1") (pintype "passive"))
    )
    (net (code "70") (name "RP_XI") (class "Default")
      (node (ref "C28") (pin "1") (pinfunction "1_1") (pintype "passive"))
      (node (ref "IC9") (pin "30") (pinfunction "XIN_30") (pintype "input"))
      (node (ref "X1") (pin "3") (pinfunction "2_3") (pintype "passive"))
    )
    (net (code "71") (name "RP_XO") (class "Default")
      (node (ref "IC9") (pin "31") (pinfunction "XOUT_31") (pintype "output"))
      (node (ref "R6") (pin "2") (pinfunction "2_2") (pintype "passive"))
    )
    (net (code "72") (name "RUN") (class "Default")
      (node (ref "IC9") (pin "35") (pinfunction "RUN_35") (pintype "input"))
      (node (ref "M.2-M1") (pin "P$54") (pinfunction "54_P$54") (pintype "bidirectional"))
      (node (ref "R8") (pin "2") (pinfunction "2_2") (pintype "passive"))
    )
    (net (code "73") (name "SWCLK") (class "Default")
      (node (ref "IC9") (pin "33") (pinfunction "SWCLK_33") (pintype "output"))
      (node (ref "R22") (pin "2") (pinfunction "2_2") (pintype "passive"))
    )
    (net (code "74") (name "SWCLK_M2") (class "Default")
      (node (ref "M.2-M1") (pin "P$58") (pinfunction "58_P$58") (pintype "bidirectional"))
      (node (ref "R22") (pin "1") (pinfunction "1_1") (pintype "passive"))
    )
    (net (code "75") (name "SWDIO") (class "Default")
      (node (ref "IC9") (pin "34") (pinfunction "SWDIO_34") (pintype "bidirectional"))
      (node (ref "R21") (pin "2") (pinfunction "2_2") (pintype "passive"))
    )
    (net (code "76") (name "SWDIO_M2") (class "Default")
      (node (ref "M.2-M1") (pin "P$56") (pinfunction "56_P$56") (pintype "bidirectional"))
      (node (ref "R21") (pin "1") (pinfunction "1_1") (pintype "passive"))
    )
    (net (code "77") (name "USBFT_DP_N") (class "Default")
      (node (ref "IC2") (pin "6") (pinfunction "D-_6") (pintype "bidirectional"))
      (node (ref "IC7") (pin "15") (pinfunction "USBDM_15") (pintype "bidirectional"))
    )
    (net (code "78") (name "USBFT_DP_P") (class "Default")
      (node (ref "IC2") (pin "7") (pinfunction "D+_7") (pintype "bidirectional"))
      (node (ref "IC7") (pin "14") (pinfunction "USBDP_14") (pintype "bidirectional"))
    )
    (net (code "79") (name "USBRP2_DP_N") (class "Default")
      (node (ref "IC9") (pin "66") (pinfunction "USB_DM_66") (pintype "bidirectional"))
      (node (ref "R32") (pin "2") (pinfunction "2_2") (pintype "passive"))
    )
    (net (code "80") (name "USBRP2_DP_P") (class "Default")
      (node (ref "IC9") (pin "67") (pinfunction "USB_DP_67") (pintype "bidirectional"))
      (node (ref "R33") (pin "2") (pinfunction "2_2") (pintype "passive"))
    )
    (net (code "81") (name "USBRP_DP_N") (class "Default")
      (node (ref "IC2") (pin "4") (pinfunction "M-_4") (pintype "bidirectional"))
      (node (ref "R32") (pin "1") (pinfunction "1_1") (pintype "passive"))
    )
    (net (code "82") (name "USBRP_DP_P") (class "Default")
      (node (ref "IC2") (pin "5") (pinfunction "M+_5") (pintype "bidirectional"))
      (node (ref "R33") (pin "1") (pinfunction "1_1") (pintype "passive"))
    )
    (net (code "83") (name "USB_DP_N") (class "Default")
      (node (ref "IC2") (pin "2") (pinfunction "Y-_2") (pintype "bidirectional"))
      (node (ref "M.2-M1") (pin "P$53") (pinfunction "53_P$53") (pintype "bidirectional"))
    )
    (net (code "84") (name "USB_DP_P") (class "Default")
      (node (ref "IC2") (pin "1") (pinfunction "Y+_1") (pintype "bidirectional"))
      (node (ref "M.2-M1") (pin "P$55") (pinfunction "55_P$55") (pintype "bidirectional"))
    )
    (net (code "85") (name "VBUS") (class "Default")
      (node (ref "C1") (pin "1") (pinfunction "1_1") (pintype "passive"))
      (node (ref "C25") (pin "1") (pinfunction "1_1") (pintype "passive"))
      (node (ref "IC6") (pin "1") (pinfunction "VIN_1") (pintype "bidirectional"))
      (node (ref "IC6") (pin "3") (pinfunction "EN_3") (pintype "bidirectional"))
      (node (ref "IC7") (pin "19") (pinfunction "VCC_19") (pintype "power_in"))
      (node (ref "M.2-M1") (pin "P$73") (pinfunction "73_P$73") (pintype "bidirectional"))
      (node (ref "M.2-M1") (pin "P$74") (pinfunction "74_P$74") (pintype "bidirectional"))
      (node (ref "M.2-M1") (pin "P$75") (pinfunction "75_P$75") (pintype "bidirectional"))
      (node (ref "R14") (pin "2") (pinfunction "2_2") (pintype "passive"))
      (node (ref "RX") (pin "A") (pinfunction "A_A") (pintype "passive"))
      (node (ref "TX") (pin "A") (pinfunction "A_A") (pintype "passive"))
    )
    (net (code "86") (name "VCCIO") (class "Default")
      (node (ref "C3") (pin "1") (pinfunction "1_1") (pintype "passive"))
      (node (ref "C6") (pin "1") (pinfunction "1_1") (pintype "passive"))
      (node (ref "IC7") (pin "1") (pinfunction "VCCIO_1") (pintype "power_in"))
      (node (ref "R14") (pin "1") (pinfunction "1_1") (pintype "passive"))
      (node (ref "R15") (pin "2") (pinfunction "2_2") (pintype "passive"))
    )
    (net (code "87") (name "VCORE") (class "Default")
      (node (ref "C10") (pin "1") (pinfunction "1_1") (pintype "passive"))
      (node (ref "C22") (pin "1") (pinfunction "1_1") (pintype "passive"))
      (node (ref "C24") (pin "1") (pinfunction "1_1") (pintype "passive"))
      (node (ref "IC9") (pin "10") (pinfunction "DVDD1_10") (pintype "power_in"))
      (node (ref "IC9") (pin "32") (pinfunction "DVDD2_32") (pintype "power_in"))
      (node (ref "IC9") (pin "51") (pinfunction "DVDD3_51") (pintype "power_in"))
      (node (ref "J3") (pin "2") (pinfunction "2_2") (pintype "passive"))
    )
    (net (code "88") (name "VREGO") (class "Default")
      (node (ref "C11") (pin "1") (pinfunction "1_1") (pintype "passive"))
      (node (ref "IC9") (pin "65") (pinfunction "VREG_FB_65") (pintype "input"))
      (node (ref "J3") (pin "1") (pinfunction "1_1") (pintype "passive"))
      (node (ref "L1") (pin "1") (pinfunction "1_1") (pintype "passive"))
    )
    (net (code "89") (name "VREG_AVDD") (class "Default")
      (node (ref "C33") (pin "1") (pinfunction "1_1") (pintype "passive"))
      (node (ref "IC9") (pin "61") (pinfunction "VREG_AVDD_61") (pintype "power_in"))
      (node (ref "R2") (pin "2") (pinfunction "2_2") (pintype "passive"))
    )
    (net (code "90") (name "unconnected-(IC6-NC-Pad4)") (class "Default")
      (node (ref "IC6") (pin "4") (pinfunction "NC_4") (pintype "bidirectional"))
    )
    (net (code "91") (name "unconnected-(IC7-CBUS2-Pad10)") (class "Default")
      (node (ref "IC7") (pin "10") (pinfunction "CBUS2_10") (pintype "bidirectional"))
    )
    (net (code "92") (name "unconnected-(IC7-CBUS3-Pad11)") (class "Default")
      (node (ref "IC7") (pin "11") (pinfunction "CBUS3_11") (pintype "bidirectional"))
    )
    (net (code "93") (name "unconnected-(IC7-CBUS4-Pad9)") (class "Default")
      (node (ref "IC7") (pin "9") (pinfunction "CBUS4_9") (pintype "bidirectional"))
    )
    (net (code "94") (name "unconnected-(IC7-OSCI-Pad27)") (class "Default")
      (node (ref "IC7") (pin "27") (pinfunction "OSCI_27") (pintype "input"))
    )
    (net (code "95") (name "unconnected-(IC7-OSCO-Pad28)") (class "Default")
      (node (ref "IC7") (pin "28") (pinfunction "OSCO_28") (pintype "output"))
    )
    (net (code "96") (name "unconnected-(IC7-~{CTS}-Pad8)") (class "Default")
      (node (ref "IC7") (pin "8") (pinfunction "~{CTS}_8") (pintype "input"))
    )
    (net (code "97") (name "unconnected-(IC7-~{DCD}-Pad7)") (class "Default")
      (node (ref "IC7") (pin "7") (pinfunction "~{DCD}_7") (pintype "input"))
    )
    (net (code "98") (name "unconnected-(IC7-~{DSR}-Pad6)") (class "Default")
      (node (ref "IC7") (pin "6") (pinfunction "~{DSR}_6") (pintype "input"))
    )
    (net (code "99") (name "unconnected-(IC7-~{DTR}-Pad31)") (class "Default")
      (node (ref "IC7") (pin "31") (pinfunction "~{DTR}_31") (pintype "output"))
    )
    (net (code "100") (name "unconnected-(IC7-~{RESET}-Pad18)") (class "Default")
      (node (ref "IC7") (pin "18") (pinfunction "~{RESET}_18") (pintype "input"))
    )
    (net (code "101") (name "unconnected-(IC7-~{RI}-Pad3)") (class "Default")
      (node (ref "IC7") (pin "3") (pinfunction "~{RI}_3") (pintype "input"))
    )
    (net (code "102") (name "unconnected-(IC7-~{RTS}-Pad32)") (class "Default")
      (node (ref "IC7") (pin "32") (pinfunction "~{RTS}_32") (pintype "output"))
    )
    (net (code "103") (name "~{QSPI_SS}") (class "Default")
      (node (ref "IC3") (pin "C2") (pinfunction "~{CS}_C2") (pintype "bidirectional"))
      (node (ref "IC9") (pin "75") (pinfunction "QSPI_SS_75") (pintype "output"))
    )
  )
)
